# supply0.net
KiCad netlist of a schematic drawn in Altium Designer
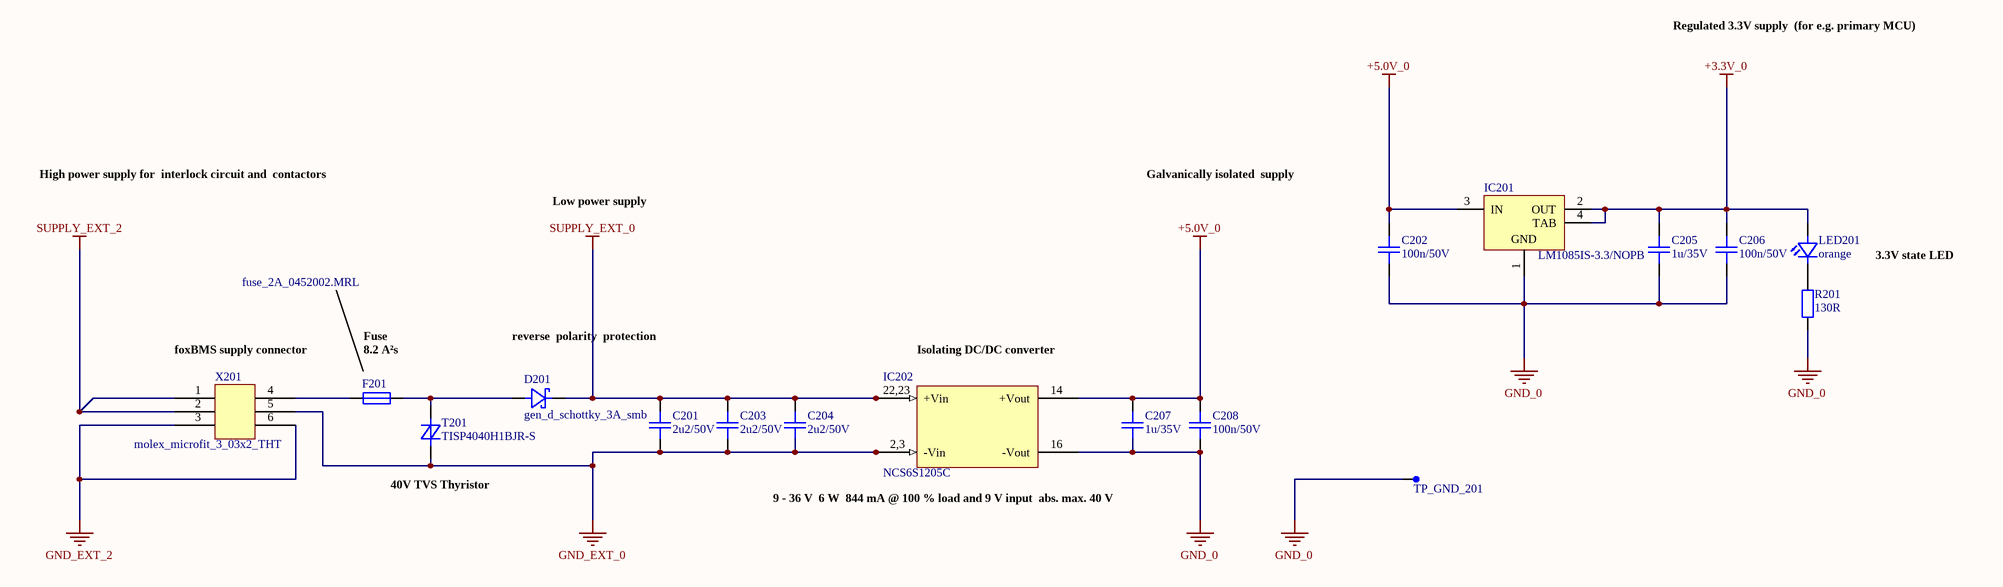
[diagram p0: supply0.SchDoc]

(export (version "E")
  (design (tool "Eeschema 10.0.6"))
  (components
    (comp (ref "C201")
      (value "2u2/50V")
      (footprint "CAPC2012X14N")
      (description "MLCC")
      (fields (field (name "PART NUMBER") "gen_C_ceramic_2u2_50V_X7R_0805"))
      (libsource (lib "OE750") (part "C"))
    )
    (comp (ref "C202")
      (value "100n/50V")
      (footprint "CAPC1608X08N")
      (description "MLCC")
      (fields (field (name "PART NUMBER") "gen_C_ceramic_100n_50V_X7R_0603"))
      (libsource (lib "OE750") (part "C"))
    )
    (comp (ref "C203")
      (value "2u2/50V")
      (footprint "CAPC2012X14N")
      (description "MLCC")
      (fields (field (name "PART NUMBER") "gen_C_ceramic_2u2_50V_X7R_0805"))
      (libsource (lib "OE750") (part "C"))
    )
    (comp (ref "C204")
      (value "2u2/50V")
      (footprint "CAPC2012X14N")
      (description "MLCC")
      (fields (field (name "PART NUMBER") "gen_C_ceramic_2u2_50V_X7R_0805"))
      (libsource (lib "OE750") (part "C"))
    )
    (comp (ref "C205")
      (value "1u/35V")
      (footprint "CAPC1608X08N")
      (description "MLCC")
      (fields (field (name "PART NUMBER") "gen_C_ceramic_1u_35V_X7R_0603"))
      (libsource (lib "OE750") (part "C"))
    )
    (comp (ref "C206")
      (value "100n/50V")
      (footprint "CAPC1608X08N")
      (description "MLCC")
      (fields (field (name "PART NUMBER") "gen_C_ceramic_100n_50V_X7R_0603"))
      (libsource (lib "OE750") (part "C"))
    )
    (comp (ref "C207")
      (value "1u/35V")
      (footprint "CAPC1608X08N")
      (description "MLCC")
      (fields (field (name "PART NUMBER") "gen_C_ceramic_1u_35V_X7R_0603"))
      (libsource (lib "OE750") (part "C"))
    )
    (comp (ref "C208")
      (value "100n/50V")
      (footprint "CAPC1608X08N")
      (description "MLCC")
      (fields (field (name "PART NUMBER") "gen_C_ceramic_100n_50V_X7R_0603"))
      (libsource (lib "OE750") (part "C"))
    )
    (comp (ref "D201")
      (value "gen_d_schottky_3A_smb")
      (footprint "SMB")
      (description "Schottky Diode")
      (fields (field (name "MANUFACTURER") "e.g. ST Microelectronics"))
      (libsource (lib "OE750") (part "D_Schottky"))
    )
    (comp (ref "F201")
      (value "fuse_2A_0452002.MRL")
      (footprint "LITTLEFUSE_452_454")
      (description "Littlefuse NANO SLO-BLO Fuse 2A 8.20A²s 0452002.MRL")
      (fields (field (name "MANUFACTURER") "Littlefuse"))
      (libsource (lib "OE750") (part "R_Fuse"))
    )
    (comp (ref "IC201")
      (value "LM1085IS-3.3/NOPB")
      (footprint "KTT0003B_N")
      (description "3A Low Dropout Positive Regulators, 3-pin TO-263, Pb-Free")
      (fields (field (name "MANUFACTURER") "Texas Instruments"))
      (libsource (lib "Altium Content Vault") (part "PM-REG-LM1086-SOT4"))
    )
    (comp (ref "IC202")
      (value "NCS6S1205C")
      (footprint "NCS6S1205C")
      (description "Murata Isolated 6W 4:1 Input Single Output DC/DC Converter")
      (fields (field (name "MANUFACTURER") "Murata Power Solutions Inc."))
      (libsource (lib "OE750") (part "NCS6S1205C"))
    )
    (comp (ref "LED201")
      (value "orange")
      (footprint "LEDC1608X07N")
      (description "LED")
      (fields (field (name "PART NUMBER") "gen_LED_0603_orange"))
      (libsource (lib "OE750") (part "D_LED"))
    )
    (comp (ref "R201")
      (value "130R")
      (footprint "RESC1608X05N")
      (description "SMD Resistor 130R 0603")
      (fields (field (name "PART NUMBER") "gen_R_130R_0603") (field (name "TOLERANCE") "1%"))
      (libsource (lib "OE750") (part "R"))
    )
    (comp (ref "T201")
      (value "TISP4040H1BJR-S")
      (footprint "SMB")
      (description "BIDIRECTIONAL THYRISTOR OVERVOLTAGE PROTECTOR")
      (fields (field (name "MANUFACTURER") "Bourns"))
      (libsource (lib "OE750") (part "TISP4040H1BJR-S"))
    )
    (comp (ref "TP_GND_201")
      (value "Testpoint_Round")
      (footprint "Testpoint_D1V")
      (description "Testpoint, Via, round")
      (fields (field (name "PART NUMBER") "Testpoint_Round_Via"))
      (libsource (lib "OE750") (part "Testpoint_Round"))
    )
    (comp (ref "X201")
      (value "molex_microfit_3_03x2_THT")
      (footprint "MOLEX_MICROFIT_03x2_THT")
      (fields (field (name "MANUFACTURER") "Molex"))
      (libsource (lib "OE750") (part "X3x2"))
    )
  )
  (nets
    (net (code "1") (name "+3.3V_0") (class "Default")
      (node (ref "C205") (pin "1") (pinfunction "1_1") (pintype "passive"))
      (node (ref "C206") (pin "1") (pinfunction "1_1") (pintype "passive"))
      (node (ref "IC201") (pin "2") (pinfunction "OUT_2") (pintype "power_in"))
      (node (ref "IC201") (pin "4") (pinfunction "TAB_4") (pintype "power_in"))
      (node (ref "LED201") (pin "2") (pinfunction "A_2") (pintype "passive"))
    )
    (net (code "2") (name "+5.0V_0") (class "Default")
      (node (ref "C202") (pin "1") (pinfunction "1_1") (pintype "passive"))
      (node (ref "C207") (pin "1") (pinfunction "1_1") (pintype "passive"))
      (node (ref "C208") (pin "1") (pinfunction "1_1") (pintype "passive"))
      (node (ref "IC201") (pin "3") (pinfunction "IN_3") (pintype "power_in"))
      (node (ref "IC202") (pin "14") (pinfunction "+Vout_14") (pintype "power_in"))
    )
    (net (code "3") (name "GND_0") (class "Default")
      (node (ref "C202") (pin "2") (pinfunction "2_2") (pintype "passive"))
      (node (ref "C205") (pin "2") (pinfunction "2_2") (pintype "passive"))
      (node (ref "C206") (pin "2") (pinfunction "2_2") (pintype "passive"))
      (node (ref "C207") (pin "2") (pinfunction "2_2") (pintype "passive"))
      (node (ref "C208") (pin "2") (pinfunction "2_2") (pintype "passive"))
      (node (ref "IC201") (pin "1") (pinfunction "GND_1") (pintype "power_in"))
      (node (ref "IC202") (pin "16") (pinfunction "-Vout_16") (pintype "power_in"))
      (node (ref "R201") (pin "1") (pinfunction "1_1") (pintype "passive"))
      (node (ref "TP_GND_201") (pin "1") (pinfunction "1_1") (pintype "passive"))
    )
    (net (code "4") (name "GND_EXT_0") (class "Default")
      (node (ref "C201") (pin "2") (pinfunction "2_2") (pintype "passive"))
      (node (ref "C203") (pin "2") (pinfunction "2_2") (pintype "passive"))
      (node (ref "C204") (pin "2") (pinfunction "2_2") (pintype "passive"))
      (node (ref "IC202") (pin "2") (pinfunction "-Vin_2") (pintype "input"))
      (node (ref "IC202") (pin "3") (pinfunction "-Vin_3") (pintype "input"))
      (node (ref "T201") (pin "2") (pinfunction "T(A)_2") (pintype "passive"))
      (node (ref "X201") (pin "5") (pintype "passive"))
    )
    (net (code "5") (name "GND_EXT_2") (class "Default")
      (node (ref "X201") (pin "3") (pintype "passive"))
      (node (ref "X201") (pin "6") (pintype "passive"))
    )
    (net (code "6") (name "Net-(D201-A)") (class "Default")
      (node (ref "D201") (pin "2") (pinfunction "A_2") (pintype "passive"))
      (node (ref "F201") (pin "2") (pinfunction "2_2") (pintype "passive"))
      (node (ref "T201") (pin "1") (pinfunction "R(B)_1") (pintype "passive"))
    )
    (net (code "7") (name "Net-(F201-Pad1)") (class "Default")
      (node (ref "F201") (pin "1") (pinfunction "1_1") (pintype "passive"))
      (node (ref "X201") (pin "4") (pintype "passive"))
    )
    (net (code "8") (name "Net-(LED201-C)") (class "Default")
      (node (ref "LED201") (pin "1") (pinfunction "C_1") (pintype "passive"))
      (node (ref "R201") (pin "2") (pinfunction "2_2") (pintype "passive"))
    )
    (net (code "9") (name "SUPPLY_EXT_0") (class "Default")
      (node (ref "C201") (pin "1") (pinfunction "1_1") (pintype "passive"))
      (node (ref "C203") (pin "1") (pinfunction "1_1") (pintype "passive"))
      (node (ref "C204") (pin "1") (pinfunction "1_1") (pintype "passive"))
      (node (ref "D201") (pin "1") (pinfunction "K_1") (pintype "passive"))
      (node (ref "IC202") (pin "22") (pinfunction "+Vin_22") (pintype "input"))
      (node (ref "IC202") (pin "23") (pinfunction "+Vin_23") (pintype "input"))
    )
    (net (code "10") (name "SUPPLY_EXT_2") (class "Default")
      (node (ref "X201") (pin "1") (pintype "passive"))
      (node (ref "X201") (pin "2") (pintype "passive"))
    )
  )
)
